# lightmeter_external_batt_ldo.net
KiCad netlist of a schematic drawn in EAGLE
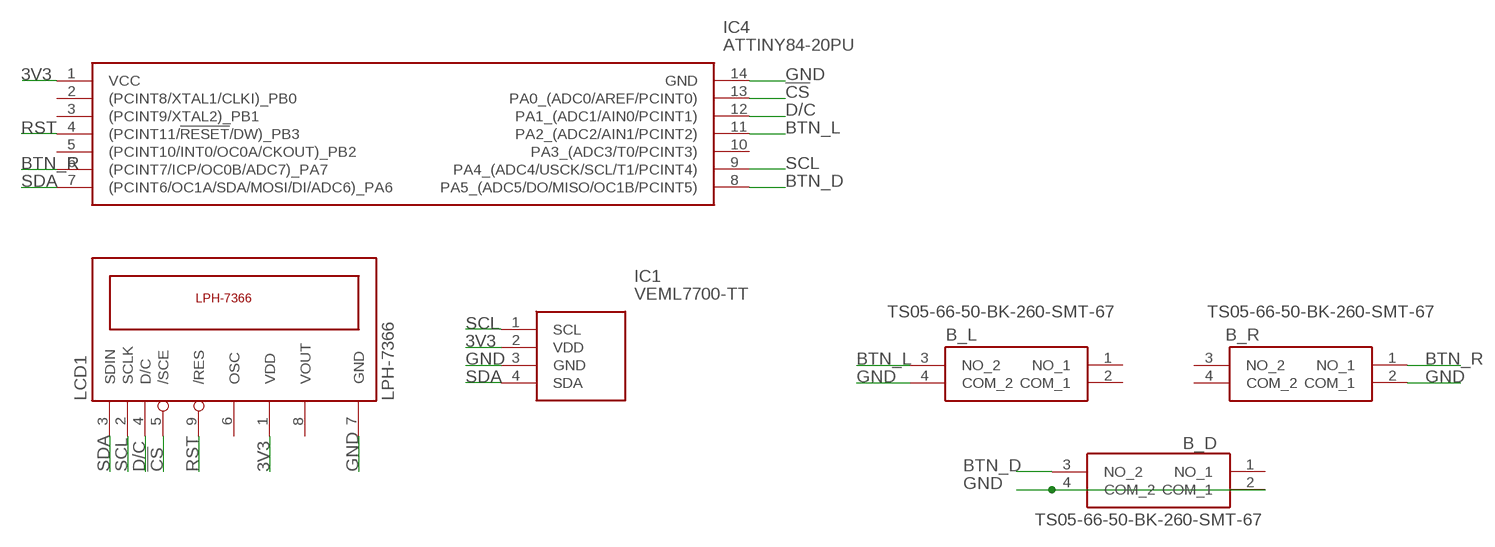
[diagram p0: schematic, sheet 1]

(export (version "E")
  (design (tool "Eeschema 10.0.6"))
  (components
    (comp (ref "B_D")
      (value "TS05-66-50-BK-260-SMT-67")
      (footprint "eagle-import:TS056650BK260SMT67")
      (fields (field (name "MOUSER_PART_NUMBER") "179-TS056650260SMT67"))
      (libsource (lib "eagle-import") (part "TS05-66-50-BK-260-SMT-67"))
    )
    (comp (ref "B_L")
      (value "TS05-66-50-BK-260-SMT-67")
      (footprint "eagle-import:TS056650BK260SMT67")
      (fields (field (name "MOUSER_PART_NUMBER") "179-TS056650260SMT67"))
      (libsource (lib "eagle-import") (part "TS05-66-50-BK-260-SMT-67"))
    )
    (comp (ref "B_R")
      (value "TS05-66-50-BK-260-SMT-67")
      (footprint "eagle-import:TS056650BK260SMT67")
      (fields (field (name "MOUSER_PART_NUMBER") "179-TS056650260SMT67"))
      (libsource (lib "eagle-import") (part "TS05-66-50-BK-260-SMT-67"))
    )
    (comp (ref "IC1")
      (value "VEML7700-TT")
      (footprint "eagle-import:VEML7700")
      (fields (field (name "MOUSER_PART_NUMBER") "78-VEML7700-TT"))
      (libsource (lib "eagle-import") (part "VEML7700-TT"))
    )
    (comp (ref "IC4")
      (value "ATTINY84-20PU")
      (footprint "eagle-import:DIP794W56P254L1918H533Q14N")
      (fields (field (name "MOUSER_PART_NUMBER") "556-ATTINY84-20PU"))
      (libsource (lib "eagle-import") (part "ATTINY84-20PU"))
    )
    (comp (ref "LCD1")
      (value "LPH-7366")
      (footprint "eagle-import:LPH-7366")
      (libsource (lib "eagle-import") (part "LPH-7366"))
    )
  )
  (nets
    (net (code "1") (name "/3V3") (class "Default")
      (node (ref "IC1") (pin "2") (pinfunction "VDD_2") (pintype "bidirectional"))
      (node (ref "IC4") (pin "1") (pinfunction "VCC_1") (pintype "bidirectional"))
      (node (ref "LCD1") (pin "1") (pinfunction "VDD_1") (pintype "power_in"))
    )
    (net (code "2") (name "/BTN_D") (class "Default")
      (node (ref "B_D") (pin "3") (pinfunction "NO_2_3") (pintype "bidirectional"))
      (node (ref "IC4") (pin "8") (pinfunction "PA5_(ADC5/DO/MISO/OC1B/PCINT5)_8") (pintype "bidirectional"))
    )
    (net (code "3") (name "/BTN_L") (class "Default")
      (node (ref "B_L") (pin "3") (pinfunction "NO_2_3") (pintype "bidirectional"))
      (node (ref "IC4") (pin "11") (pinfunction "PA2_(ADC2/AIN1/PCINT2)_11") (pintype "bidirectional"))
    )
    (net (code "4") (name "/BTN_R") (class "Default")
      (node (ref "B_R") (pin "1") (pinfunction "NO_1_1") (pintype "bidirectional"))
      (node (ref "IC4") (pin "6") (pinfunction "(PCINT7/ICP/OC0B/ADC7)_PA7_6") (pintype "bidirectional"))
    )
    (net (code "5") (name "/D{slash}C") (class "Default")
      (node (ref "IC4") (pin "12") (pinfunction "PA1_(ADC1/AIN0/PCINT1)_12") (pintype "bidirectional"))
      (node (ref "LCD1") (pin "4") (pinfunction "D/C_4") (pintype "input"))
    )
    (net (code "6") (name "/GND") (class "Default")
      (node (ref "B_D") (pin "2") (pinfunction "COM_1_2") (pintype "bidirectional"))
      (node (ref "B_D") (pin "4") (pinfunction "COM_2_4") (pintype "bidirectional"))
      (node (ref "B_L") (pin "4") (pinfunction "COM_2_4") (pintype "bidirectional"))
      (node (ref "B_R") (pin "2") (pinfunction "COM_1_2") (pintype "bidirectional"))
      (node (ref "IC1") (pin "3") (pinfunction "GND_3") (pintype "bidirectional"))
      (node (ref "IC4") (pin "14") (pinfunction "GND_14") (pintype "bidirectional"))
      (node (ref "LCD1") (pin "7") (pinfunction "GND_7") (pintype "power_in"))
    )
    (net (code "7") (name "/RST") (class "Default")
      (node (ref "IC4") (pin "4") (pinfunction "(PCINT11/~{RESET}/DW)_PB3_4") (pintype "bidirectional"))
      (node (ref "LCD1") (pin "9") (pinfunction "/RES_9") (pintype "input"))
    )
    (net (code "8") (name "/SCL") (class "Default")
      (node (ref "IC1") (pin "1") (pinfunction "SCL_1") (pintype "bidirectional"))
      (node (ref "IC4") (pin "9") (pinfunction "PA4_(ADC4/USCK/SCL/T1/PCINT4)_9") (pintype "bidirectional"))
      (node (ref "LCD1") (pin "2") (pinfunction "SCLK_2") (pintype "input"))
    )
    (net (code "9") (name "/SDA") (class "Default")
      (node (ref "IC1") (pin "4") (pinfunction "SDA_4") (pintype "bidirectional"))
      (node (ref "IC4") (pin "7") (pinfunction "(PCINT6/OC1A/SDA/MOSI/DI/ADC6)_PA6_7") (pintype "bidirectional"))
      (node (ref "LCD1") (pin "3") (pinfunction "SDIN_3") (pintype "input"))
    )
    (net (code "10") (name "/~{CS}") (class "Default")
      (node (ref "IC4") (pin "13") (pinfunction "PA0_(ADC0/AREF/PCINT0)_13") (pintype "bidirectional"))
      (node (ref "LCD1") (pin "5") (pinfunction "/SCE_5") (pintype "input"))
    )
    (net (code "11") (name "unconnected-(B_D-NO_1-Pad1)") (class "Default")
      (node (ref "B_D") (pin "1") (pinfunction "NO_1_1") (pintype "bidirectional"))
    )
    (net (code "12") (name "unconnected-(B_L-COM_1-Pad2)") (class "Default")
      (node (ref "B_L") (pin "2") (pinfunction "COM_1_2") (pintype "bidirectional"))
    )
    (net (code "13") (name "unconnected-(B_L-NO_1-Pad1)") (class "Default")
      (node (ref "B_L") (pin "1") (pinfunction "NO_1_1") (pintype "bidirectional"))
    )
    (net (code "14") (name "unconnected-(B_R-COM_2-Pad4)") (class "Default")
      (node (ref "B_R") (pin "4") (pinfunction "COM_2_4") (pintype "bidirectional"))
    )
    (net (code "15") (name "unconnected-(B_R-NO_2-Pad3)") (class "Default")
      (node (ref "B_R") (pin "3") (pinfunction "NO_2_3") (pintype "bidirectional"))
    )
    (net (code "16") (name "unconnected-(IC4-(PCINT8{slash}XTAL1{slash}CLKI)_PB0-Pad2)") (class "Default")
      (node (ref "IC4") (pin "2") (pinfunction "(PCINT8/XTAL1/CLKI)_PB0_2") (pintype "bidirectional"))
    )
    (net (code "17") (name "unconnected-(IC4-(PCINT9{slash}XTAL2)_PB1-Pad3)") (class "Default")
      (node (ref "IC4") (pin "3") (pinfunction "(PCINT9/XTAL2)_PB1_3") (pintype "bidirectional"))
    )
    (net (code "18") (name "unconnected-(IC4-(PCINT10{slash}INT0{slash}OC0A{slash}CKOUT)_PB2-Pad5)") (class "Default")
      (node (ref "IC4") (pin "5") (pinfunction "(PCINT10/INT0/OC0A/CKOUT)_PB2_5") (pintype "bidirectional"))
    )
    (net (code "19") (name "unconnected-(IC4-PA3_(ADC3{slash}T0{slash}PCINT3)-Pad10)") (class "Default")
      (node (ref "IC4") (pin "10") (pinfunction "PA3_(ADC3/T0/PCINT3)_10") (pintype "bidirectional"))
    )
    (net (code "20") (name "unconnected-(LCD1-OSC-Pad6)") (class "Default")
      (node (ref "LCD1") (pin "6") (pinfunction "OSC_6") (pintype "passive"))
    )
    (net (code "21") (name "unconnected-(LCD1-VOUT-Pad8)") (class "Default")
      (node (ref "LCD1") (pin "8") (pinfunction "VOUT_8") (pintype "passive"))
    )
  )
)
